# tracker.net
KiCad netlist of a schematic drawn in EAGLE
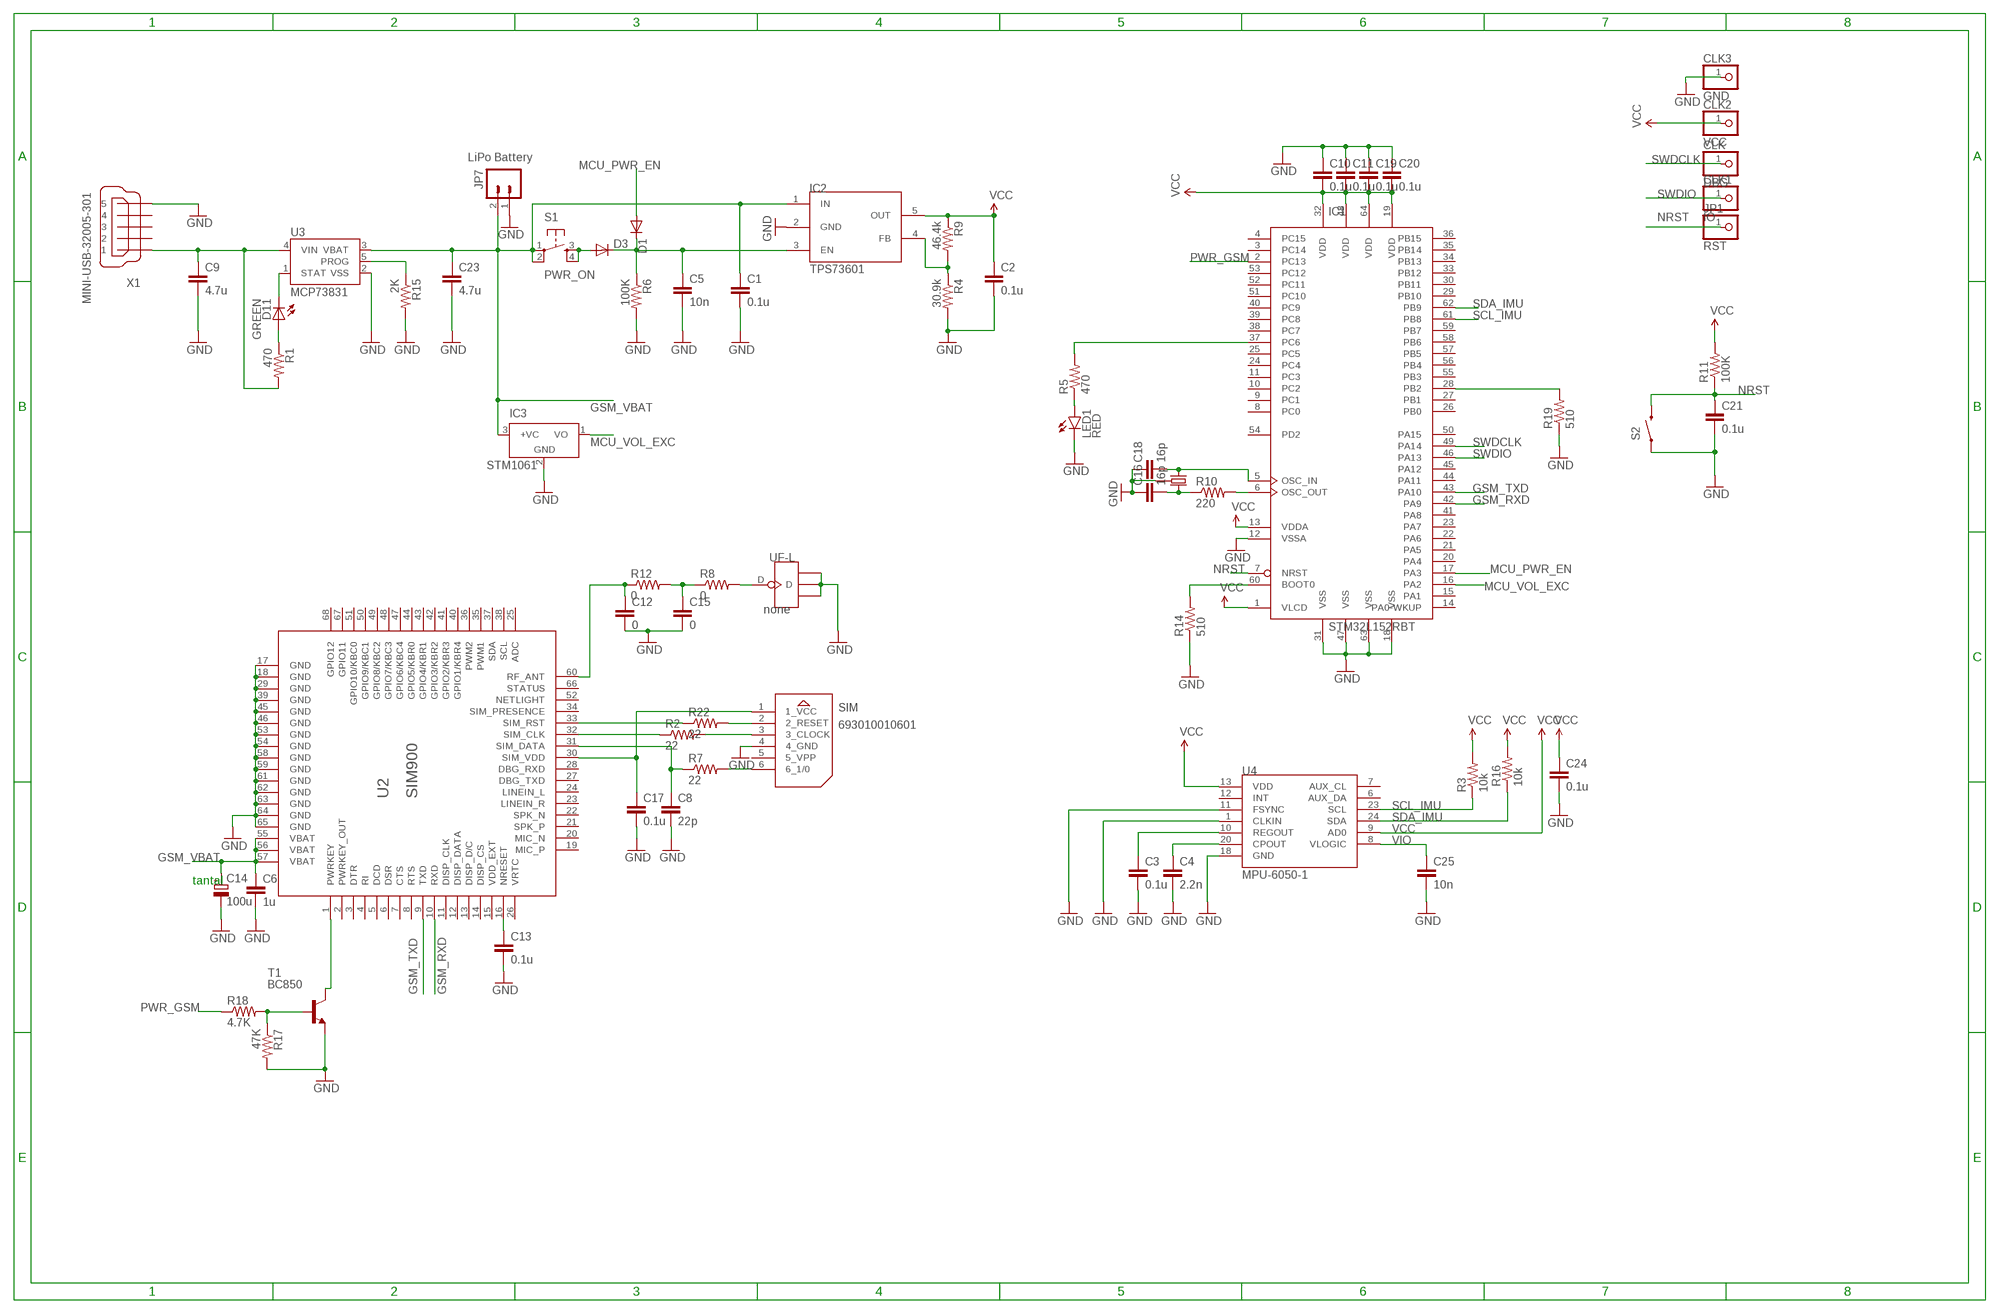
[diagram p0: schematic, sheet 1]

(export (version "E")
  (design (tool "Eeschema 10.0.6"))
  (components
    (comp (ref "C1")
      (value "0.1u")
      (footprint "eagle-import:0805")
      (libsource (lib "eagle-import") (part "CAP0805"))
    )
    (comp (ref "C2")
      (value "0.1u")
      (footprint "eagle-import:0805")
      (libsource (lib "eagle-import") (part "CAP0805"))
    )
    (comp (ref "C3")
      (value "0.1u")
      (footprint "eagle-import:0805")
      (libsource (lib "eagle-import") (part "CAP0805"))
    )
    (comp (ref "C4")
      (value "2.2n")
      (footprint "eagle-import:0805")
      (libsource (lib "eagle-import") (part "CAP0805"))
    )
    (comp (ref "C5")
      (value "10n")
      (footprint "eagle-import:0805")
      (libsource (lib "eagle-import") (part "CAP0805"))
    )
    (comp (ref "C6")
      (value "1u")
      (footprint "eagle-import:0805")
      (libsource (lib "eagle-import") (part "CAP0805"))
    )
    (comp (ref "C8")
      (value "22p")
      (footprint "eagle-import:0805")
      (libsource (lib "eagle-import") (part "CAP0805"))
    )
    (comp (ref "C9")
      (value "4.7u")
      (footprint "eagle-import:0805")
      (libsource (lib "eagle-import") (part "CAP0805"))
    )
    (comp (ref "C10")
      (value "0.1u")
      (footprint "eagle-import:0805")
      (libsource (lib "eagle-import") (part "CAP0805"))
    )
    (comp (ref "C11")
      (value "0.1u")
      (footprint "eagle-import:0805")
      (libsource (lib "eagle-import") (part "CAP0805"))
    )
    (comp (ref "C12")
      (value "0")
      (footprint "eagle-import:0805")
      (libsource (lib "eagle-import") (part "CAP0805"))
    )
    (comp (ref "C13")
      (value "0.1u")
      (footprint "eagle-import:0805")
      (libsource (lib "eagle-import") (part "CAP0805"))
    )
    (comp (ref "C14")
      (value "100u")
      (footprint "eagle-import:C_6032-28R")
      (libsource (lib "eagle-import") (part "CPOL-EUC/6032-28R"))
    )
    (comp (ref "C15")
      (value "0")
      (footprint "eagle-import:0805")
      (libsource (lib "eagle-import") (part "CAP0805"))
    )
    (comp (ref "C16")
      (value "16p")
      (footprint "eagle-import:0603-CAP")
      (libsource (lib "eagle-import") (part "CAP0603-CAP"))
    )
    (comp (ref "C17")
      (value "0.1u")
      (footprint "eagle-import:0805")
      (libsource (lib "eagle-import") (part "CAP0805"))
    )
    (comp (ref "C18")
      (value "16p")
      (footprint "eagle-import:0603-CAP")
      (libsource (lib "eagle-import") (part "CAP0603-CAP"))
    )
    (comp (ref "C19")
      (value "0.1u")
      (footprint "eagle-import:0805")
      (libsource (lib "eagle-import") (part "CAP0805"))
    )
    (comp (ref "C20")
      (value "0.1u")
      (footprint "eagle-import:0805")
      (libsource (lib "eagle-import") (part "CAP0805"))
    )
    (comp (ref "C21")
      (value "0.1u")
      (footprint "eagle-import:0805")
      (libsource (lib "eagle-import") (part "CAP0805"))
    )
    (comp (ref "C23")
      (value "4.7u")
      (footprint "eagle-import:0805")
      (libsource (lib "eagle-import") (part "CAP0805"))
    )
    (comp (ref "C24")
      (value "0.1u")
      (footprint "eagle-import:0805")
      (libsource (lib "eagle-import") (part "CAP0805"))
    )
    (comp (ref "C25")
      (value "10n")
      (footprint "eagle-import:0805")
      (libsource (lib "eagle-import") (part "CAP0805"))
    )
    (comp (ref "CLK")
      (value "DBG")
      (footprint "eagle-import:1X01")
      (libsource (lib "eagle-import") (part "PINHD-1X1"))
    )
    (comp (ref "CLK1")
      (value "IO")
      (footprint "eagle-import:1X01")
      (libsource (lib "eagle-import") (part "PINHD-1X1"))
    )
    (comp (ref "CLK2")
      (value "VCC")
      (footprint "eagle-import:1X01")
      (libsource (lib "eagle-import") (part "PINHD-1X1"))
    )
    (comp (ref "CLK3")
      (value "GND")
      (footprint "eagle-import:1X01")
      (libsource (lib "eagle-import") (part "PINHD-1X1"))
    )
    (comp (ref "D1")
      (value "MBR0520LT")
      (footprint "eagle-import:SOD123")
      (libsource (lib "eagle-import") (part "MBR0520LT"))
    )
    (comp (ref "D3")
      (value "MBR0520LT")
      (footprint "eagle-import:SOD123")
      (libsource (lib "eagle-import") (part "MBR0520LT"))
    )
    (comp (ref "D11")
      (value "GREEN")
      (footprint "eagle-import:LED-0603")
      (libsource (lib "eagle-import") (part "LED0603"))
    )
    (comp (ref "IC1")
      (value "STM32L152RBT")
      (footprint "eagle-import:LQFP64")
      (libsource (lib "eagle-import") (part "STM32L152RTB"))
    )
    (comp (ref "IC2")
      (value "TPS73601")
      (footprint "eagle-import:SOT23")
      (libsource (lib "eagle-import") (part "TPS73601"))
    )
    (comp (ref "IC3")
      (value "LM50")
      (footprint "eagle-import:SOT23")
      (libsource (lib "eagle-import") (part "LM50"))
    )
    (comp (ref "JP1")
      (value "RST")
      (footprint "eagle-import:1X01")
      (libsource (lib "eagle-import") (part "PINHD-1X1"))
    )
    (comp (ref "JP7")
      (value "LiPo Battery")
      (footprint "eagle-import:JST-2-SMD")
      (libsource (lib "eagle-import") (part "M02-JST-2MM-SMT"))
    )
    (comp (ref "LED1")
      (value "RED")
      (footprint "eagle-import:LED-0603")
      (libsource (lib "eagle-import") (part "LED-RED0603"))
    )
    (comp (ref "R1")
      (value "470")
      (footprint "eagle-import:0805")
      (libsource (lib "eagle-import") (part "RESISTOR0805-RES"))
    )
    (comp (ref "R2")
      (value "22")
      (footprint "eagle-import:0805")
      (libsource (lib "eagle-import") (part "RESISTOR0805-RES"))
    )
    (comp (ref "R3")
      (value "10k")
      (footprint "eagle-import:0805")
      (libsource (lib "eagle-import") (part "RESISTOR0805-RES"))
    )
    (comp (ref "R4")
      (value "30.9k")
      (footprint "eagle-import:0805")
      (libsource (lib "eagle-import") (part "RESISTOR0805-RES"))
    )
    (comp (ref "R5")
      (value "470")
      (footprint "eagle-import:0805")
      (libsource (lib "eagle-import") (part "RESISTOR0805-RES"))
    )
    (comp (ref "R6")
      (value "100K")
      (footprint "eagle-import:0805")
      (libsource (lib "eagle-import") (part "RESISTOR0805-RES"))
    )
    (comp (ref "R7")
      (value "22")
      (footprint "eagle-import:0805")
      (libsource (lib "eagle-import") (part "RESISTOR0805-RES"))
    )
    (comp (ref "R8")
      (value "0")
      (footprint "eagle-import:0805")
      (libsource (lib "eagle-import") (part "RESISTOR0805-RES"))
    )
    (comp (ref "R9")
      (value "46.4k")
      (footprint "eagle-import:0805")
      (libsource (lib "eagle-import") (part "RESISTOR0805-RES"))
    )
    (comp (ref "R10")
      (value "220")
      (footprint "eagle-import:0805")
      (libsource (lib "eagle-import") (part "RESISTOR0805-RES"))
    )
    (comp (ref "R11")
      (value "100K")
      (footprint "eagle-import:0805")
      (libsource (lib "eagle-import") (part "RESISTOR0805-RES"))
    )
    (comp (ref "R12")
      (value "0")
      (footprint "eagle-import:0805")
      (libsource (lib "eagle-import") (part "RESISTOR0805-RES"))
    )
    (comp (ref "R14")
      (value "510")
      (footprint "eagle-import:0805")
      (libsource (lib "eagle-import") (part "RESISTOR0805-RES"))
    )
    (comp (ref "R15")
      (value "2K")
      (footprint "eagle-import:0805")
      (libsource (lib "eagle-import") (part "RESISTOR0805-RES"))
    )
    (comp (ref "R16")
      (value "10k")
      (footprint "eagle-import:0805")
      (libsource (lib "eagle-import") (part "RESISTOR0805-RES"))
    )
    (comp (ref "R17")
      (value "47K")
      (footprint "eagle-import:0805")
      (libsource (lib "eagle-import") (part "RESISTOR0805-RES"))
    )
    (comp (ref "R18")
      (value "4.7K")
      (footprint "eagle-import:0805")
      (libsource (lib "eagle-import") (part "RESISTOR0805-RES"))
    )
    (comp (ref "R19")
      (value "510")
      (footprint "eagle-import:0805")
      (libsource (lib "eagle-import") (part "RESISTOR0805-RES"))
    )
    (comp (ref "R22")
      (value "22")
      (footprint "eagle-import:0805")
      (libsource (lib "eagle-import") (part "RESISTOR0805-RES"))
    )
    (comp (ref "S1")
      (value "PWR_ON")
      (footprint "eagle-import:TACTILE-PTH")
      (libsource (lib "eagle-import") (part "TAC_SWITCHPTH"))
    )
    (comp (ref "S2")
      (value "SWITCH-MOMENTARY-2SMD-REDUNDANT")
      (footprint "eagle-import:TACTILE-SWITCH-SMD")
      (libsource (lib "eagle-import") (part "SWITCH-MOMENTARY-2SMD-REDUNDANT"))
    )
    (comp (ref "SIM")
      (value "693010010601")
      (footprint "eagle-import:693010010601")
      (libsource (lib "eagle-import") (part "693010010601"))
    )
    (comp (ref "T1")
      (value "BC850")
      (footprint "eagle-import:SOT23")
      (libsource (lib "eagle-import") (part "BC850"))
    )
    (comp (ref "U$1")
      (value "CRYSTAL-GROUNDED")
      (footprint "eagle-import:CRYSTAL-SMD-5X3")
      (libsource (lib "eagle-import") (part "CRYSTAL-GROUNDED"))
    )
    (comp (ref "U2")
      (value "SIM900")
      (footprint "eagle-import:SIM900")
      (libsource (lib "eagle-import") (part "SIM900"))
    )
    (comp (ref "U3")
      (value "MCP73831")
      (footprint "eagle-import:SOT23-5")
      (libsource (lib "eagle-import") (part "MCP73831"))
    )
    (comp (ref "U4")
      (value "MPU-6050-1")
      (footprint "eagle-import:QFN-24-4MM2")
      (libsource (lib "eagle-import") (part "MPU-6050-1"))
    )
    (comp (ref "UF-L")
      (value "none")
      (footprint "eagle-import:4P-U-FL")
      (libsource (lib "eagle-import") (part "ANTENNA-U-FL"))
    )
    (comp (ref "X1")
      (value "MINI-USB-32005-301")
      (footprint "eagle-import:32005-301")
      (libsource (lib "eagle-import") (part "MINI-USB-32005-301"))
    )
  )
  (nets
    (net (code "1") (name "/GSM_RXD") (class "Default")
      (node (ref "IC1") (pin "42") (pinfunction "PA9_42") (pintype "bidirectional"))
      (node (ref "U2") (pin "10") (pinfunction "RXD_10") (pintype "input"))
    )
    (net (code "2") (name "/GSM_TXD") (class "Default")
      (node (ref "IC1") (pin "43") (pinfunction "PA10_43") (pintype "bidirectional"))
      (node (ref "U2") (pin "9") (pinfunction "TXD_9") (pintype "output"))
    )
    (net (code "3") (name "/GSM_VBAT") (class "Default")
      (node (ref "C1") (pin "1") (pinfunction "1_1") (pintype "passive"))
      (node (ref "C14") (pin "+") (pinfunction "+_+") (pintype "passive"))
      (node (ref "C23") (pin "1") (pinfunction "1_1") (pintype "passive"))
      (node (ref "C6") (pin "1") (pinfunction "1_1") (pintype "passive"))
      (node (ref "IC2") (pin "1") (pinfunction "IN_1") (pintype "power_in"))
      (node (ref "IC3") (pin "3") (pinfunction "+VC_3") (pintype "input"))
      (node (ref "JP7") (pin "2") (pinfunction "2_2") (pintype "passive"))
      (node (ref "S1") (pin "1") (pinfunction "1_1") (pintype "passive"))
      (node (ref "S1") (pin "2") (pinfunction "2_2") (pintype "passive"))
      (node (ref "U2") (pin "55") (pinfunction "VBAT_55") (pintype "power_in"))
      (node (ref "U2") (pin "56") (pinfunction "VBAT_56") (pintype "power_in"))
      (node (ref "U2") (pin "57") (pinfunction "VBAT_57") (pintype "power_in"))
      (node (ref "U3") (pin "3") (pinfunction "VBAT_3") (pintype "power_in"))
    )
    (net (code "4") (name "/MCU_PWR_EN") (class "Default")
      (node (ref "D1") (pin "A") (pinfunction "A_A") (pintype "passive"))
      (node (ref "IC1") (pin "17") (pinfunction "PA3_17") (pintype "bidirectional"))
    )
    (net (code "5") (name "/MCU_VOL_EXC") (class "Default")
      (node (ref "IC1") (pin "16") (pinfunction "PA2_16") (pintype "bidirectional"))
      (node (ref "IC3") (pin "1") (pinfunction "VO_1") (pintype "input"))
    )
    (net (code "6") (name "/NRST") (class "Default")
      (node (ref "C21") (pin "1") (pinfunction "1_1") (pintype "passive"))
      (node (ref "IC1") (pin "7") (pinfunction "NRST_7") (pintype "bidirectional"))
      (node (ref "JP1") (pin "1") (pinfunction "1_1") (pintype "passive"))
      (node (ref "R11") (pin "1") (pinfunction "1_1") (pintype "passive"))
      (node (ref "S2") (pin "3") (pinfunction "2_3") (pintype "passive"))
      (node (ref "S2") (pin "4") (pinfunction "2_4") (pintype "passive"))
    )
    (net (code "7") (name "/PWR_GSM") (class "Default")
      (node (ref "IC1") (pin "2") (pinfunction "PC13_2") (pintype "bidirectional"))
      (node (ref "R18") (pin "1") (pinfunction "1_1") (pintype "passive"))
    )
    (net (code "8") (name "/SCL_IMU") (class "Default")
      (node (ref "IC1") (pin "61") (pinfunction "PB8_61") (pintype "bidirectional"))
      (node (ref "R3") (pin "1") (pinfunction "1_1") (pintype "passive"))
      (node (ref "U4") (pin "23") (pinfunction "SCL_23") (pintype "bidirectional"))
    )
    (net (code "9") (name "/SDA_IMU") (class "Default")
      (node (ref "IC1") (pin "62") (pinfunction "PB9_62") (pintype "bidirectional"))
      (node (ref "R16") (pin "1") (pinfunction "1_1") (pintype "passive"))
      (node (ref "U4") (pin "24") (pinfunction "SDA_24") (pintype "bidirectional"))
    )
    (net (code "10") (name "/SWDCLK") (class "Default")
      (node (ref "CLK") (pin "1") (pinfunction "1_1") (pintype "passive"))
      (node (ref "IC1") (pin "49") (pinfunction "PA14_49") (pintype "bidirectional"))
    )
    (net (code "11") (name "/SWDIO") (class "Default")
      (node (ref "CLK1") (pin "1") (pinfunction "1_1") (pintype "passive"))
      (node (ref "IC1") (pin "46") (pinfunction "PA13_46") (pintype "bidirectional"))
    )
    (net (code "12") (name "/VIO") (class "Default")
      (node (ref "C25") (pin "1") (pinfunction "1_1") (pintype "passive"))
      (node (ref "U4") (pin "8") (pinfunction "VLOGIC_8") (pintype "bidirectional"))
    )
    (net (code "13") (name "GND") (class "Default")
      (node (ref "C1") (pin "2") (pinfunction "2_2") (pintype "passive"))
      (node (ref "C10") (pin "1") (pinfunction "1_1") (pintype "passive"))
      (node (ref "C11") (pin "1") (pinfunction "1_1") (pintype "passive"))
      (node (ref "C12") (pin "2") (pinfunction "2_2") (pintype "passive"))
      (node (ref "C13") (pin "2") (pinfunction "2_2") (pintype "passive"))
      (node (ref "C14") (pin "-") (pinfunction "-_-") (pintype "passive"))
      (node (ref "C15") (pin "2") (pinfunction "2_2") (pintype "passive"))
      (node (ref "C16") (pin "1") (pinfunction "1_1") (pintype "passive"))
      (node (ref "C17") (pin "2") (pinfunction "2_2") (pintype "passive"))
      (node (ref "C18") (pin "1") (pinfunction "1_1") (pintype "passive"))
      (node (ref "C19") (pin "1") (pinfunction "1_1") (pintype "passive"))
      (node (ref "C2") (pin "2") (pinfunction "2_2") (pintype "passive"))
      (node (ref "C20") (pin "1") (pinfunction "1_1") (pintype "passive"))
      (node (ref "C21") (pin "2") (pinfunction "2_2") (pintype "passive"))
      (node (ref "C23") (pin "2") (pinfunction "2_2") (pintype "passive"))
      (node (ref "C24") (pin "2") (pinfunction "2_2") (pintype "passive"))
      (node (ref "C25") (pin "2") (pinfunction "2_2") (pintype "passive"))
      (node (ref "C3") (pin "2") (pinfunction "2_2") (pintype "passive"))
      (node (ref "C4") (pin "2") (pinfunction "2_2") (pintype "passive"))
      (node (ref "C5") (pin "2") (pinfunction "2_2") (pintype "passive"))
      (node (ref "C6") (pin "2") (pinfunction "2_2") (pintype "passive"))
      (node (ref "C8") (pin "2") (pinfunction "2_2") (pintype "passive"))
      (node (ref "C9") (pin "2") (pinfunction "2_2") (pintype "passive"))
      (node (ref "CLK3") (pin "1") (pinfunction "1_1") (pintype "passive"))
      (node (ref "IC1") (pin "12") (pinfunction "VSSA_12") (pintype "power_in"))
      (node (ref "IC1") (pin "18") (pinfunction "VSS_18") (pintype "power_in"))
      (node (ref "IC1") (pin "31") (pinfunction "VSS_31") (pintype "power_in"))
      (node (ref "IC1") (pin "47") (pinfunction "VSS_47") (pintype "power_in"))
      (node (ref "IC1") (pin "63") (pinfunction "VSS_63") (pintype "power_in"))
      (node (ref "IC2") (pin "2") (pinfunction "GND_2") (pintype "power_in"))
      (node (ref "IC3") (pin "2") (pinfunction "GND_2") (pintype "power_in"))
      (node (ref "JP7") (pin "1") (pinfunction "1_1") (pintype "passive"))
      (node (ref "LED1") (pin "C") (pinfunction "C_C") (pintype "passive"))
      (node (ref "R14") (pin "1") (pinfunction "1_1") (pintype "passive"))
      (node (ref "R15") (pin "2") (pinfunction "2_2") (pintype "passive"))
      (node (ref "R17") (pin "2") (pinfunction "2_2") (pintype "passive"))
      (node (ref "R19") (pin "1") (pinfunction "1_1") (pintype "passive"))
      (node (ref "R4") (pin "2") (pinfunction "2_2") (pintype "passive"))
      (node (ref "R6") (pin "2") (pinfunction "2_2") (pintype "passive"))
      (node (ref "S2") (pin "1") (pinfunction "1_1") (pintype "passive"))
      (node (ref "S2") (pin "2") (pinfunction "1_2") (pintype "passive"))
      (node (ref "SIM") (pin "4") (pinfunction "4_GND_4") (pintype "bidirectional"))
      (node (ref "T1") (pin "2") (pinfunction "E_2") (pintype "passive"))
      (node (ref "U$1") (pin "2") (pinfunction "3_2") (pintype "passive"))
      (node (ref "U$1") (pin "4") (pinfunction "3_4") (pintype "passive"))
      (node (ref "U2") (pin "17") (pinfunction "GND_17") (pintype "power_in"))
      (node (ref "U2") (pin "18") (pinfunction "GND_18") (pintype "power_in"))
      (node (ref "U2") (pin "29") (pinfunction "GND_29") (pintype "power_in"))
      (node (ref "U2") (pin "39") (pinfunction "GND_39") (pintype "power_in"))
      (node (ref "U2") (pin "45") (pinfunction "GND_45") (pintype "power_in"))
      (node (ref "U2") (pin "46") (pinfunction "GND_46") (pintype "power_in"))
      (node (ref "U2") (pin "53") (pinfunction "GND_53") (pintype "power_in"))
      (node (ref "U2") (pin "54") (pinfunction "GND_54") (pintype "power_in"))
      (node (ref "U2") (pin "58") (pinfunction "GND_58") (pintype "power_in"))
      (node (ref "U2") (pin "59") (pinfunction "GND_59") (pintype "power_in"))
      (node (ref "U2") (pin "61") (pinfunction "GND_61") (pintype "power_in"))
      (node (ref "U2") (pin "62") (pinfunction "GND_62") (pintype "power_in"))
      (node (ref "U2") (pin "63") (pinfunction "GND_63") (pintype "power_in"))
      (node (ref "U2") (pin "64") (pinfunction "GND_64") (pintype "power_in"))
      (node (ref "U2") (pin "65") (pinfunction "GND_65") (pintype "power_in"))
      (node (ref "U3") (pin "2") (pinfunction "VSS_2") (pintype "power_in"))
      (node (ref "U4") (pin "1") (pinfunction "CLKIN_1") (pintype "bidirectional"))
      (node (ref "U4") (pin "11") (pinfunction "FSYNC_11") (pintype "bidirectional"))
      (node (ref "U4") (pin "18") (pinfunction "GND_18") (pintype "bidirectional"))
      (node (ref "UF-L") (pin "GND1") (pinfunction "GND1_GND1") (pintype "bidirectional"))
      (node (ref "UF-L") (pin "GND2") (pinfunction "GND2_GND2") (pintype "bidirectional"))
      (node (ref "UF-L") (pin "GND3") (pinfunction "GND3_GND3") (pintype "bidirectional"))
      (node (ref "X1") (pin "5") (pinfunction "5_5") (pintype "passive"))
    )
    (net (code "14") (name "Net-(C15-Pad1)") (class "Default")
      (node (ref "C15") (pin "1") (pinfunction "1_1") (pintype "passive"))
      (node (ref "R12") (pin "2") (pinfunction "2_2") (pintype "passive"))
      (node (ref "R8") (pin "1") (pinfunction "1_1") (pintype "passive"))
    )
    (net (code "15") (name "Net-(D3-PadA)") (class "Default")
      (node (ref "D3") (pin "A") (pinfunction "A_A") (pintype "passive"))
      (node (ref "S1") (pin "3") (pinfunction "3_3") (pintype "passive"))
      (node (ref "S1") (pin "4") (pinfunction "4_4") (pintype "passive"))
    )
    (net (code "16") (name "Net-(D11-PadA)") (class "Default")
      (node (ref "D11") (pin "A") (pinfunction "A_A") (pintype "passive"))
      (node (ref "R1") (pin "1") (pinfunction "1_1") (pintype "passive"))
    )
    (net (code "17") (name "Net-(IC1A-BOOT0)") (class "Default")
      (node (ref "IC1") (pin "60") (pinfunction "BOOT0_60") (pintype "input"))
      (node (ref "R14") (pin "2") (pinfunction "2_2") (pintype "passive"))
    )
    (net (code "18") (name "Net-(IC1A-OSC_IN)") (class "Default")
      (node (ref "C18") (pin "2") (pinfunction "2_2") (pintype "passive"))
      (node (ref "IC1") (pin "5") (pinfunction "OSC_IN_5") (pintype "bidirectional"))
      (node (ref "U$1") (pin "3") (pinfunction "1_3") (pintype "passive"))
    )
    (net (code "19") (name "Net-(IC1A-OSC_OUT)") (class "Default")
      (node (ref "IC1") (pin "6") (pinfunction "OSC_OUT_6") (pintype "bidirectional"))
      (node (ref "R10") (pin "2") (pinfunction "2_2") (pintype "passive"))
    )
    (net (code "20") (name "Net-(IC1A-PB2)") (class "Default")
      (node (ref "IC1") (pin "28") (pinfunction "PB2_28") (pintype "bidirectional"))
      (node (ref "R19") (pin "2") (pinfunction "2_2") (pintype "passive"))
    )
    (net (code "21") (name "Net-(IC1A-PC6)") (class "Default")
      (node (ref "IC1") (pin "37") (pinfunction "PC6_37") (pintype "bidirectional"))
      (node (ref "R5") (pin "2") (pinfunction "2_2") (pintype "passive"))
    )
    (net (code "22") (name "Net-(IC2-EN)") (class "Default")
      (node (ref "C5") (pin "1") (pinfunction "1_1") (pintype "passive"))
      (node (ref "D1") (pin "C") (pinfunction "C_C") (pintype "passive"))
      (node (ref "D3") (pin "C") (pinfunction "C_C") (pintype "passive"))
      (node (ref "IC2") (pin "3") (pinfunction "EN_3") (pintype "passive"))
      (node (ref "R6") (pin "1") (pinfunction "1_1") (pintype "passive"))
    )
    (net (code "23") (name "Net-(IC2-FB)") (class "Default")
      (node (ref "IC2") (pin "4") (pinfunction "FB_4") (pintype "power_in"))
      (node (ref "R4") (pin "1") (pinfunction "1_1") (pintype "passive"))
      (node (ref "R9") (pin "2") (pinfunction "2_2") (pintype "passive"))
    )
    (net (code "24") (name "Net-(LED1-PadA)") (class "Default")
      (node (ref "LED1") (pin "A") (pinfunction "A_A") (pintype "passive"))
      (node (ref "R5") (pin "1") (pinfunction "1_1") (pintype "passive"))
    )
    (net (code "25") (name "Net-(R8-Pad2)") (class "Default")
      (node (ref "R8") (pin "2") (pinfunction "2_2") (pintype "passive"))
      (node (ref "UF-L") (pin "D") (pinfunction "D_D") (pintype "bidirectional"))
    )
    (net (code "26") (name "Net-(SIM-1_VCC)") (class "Default")
      (node (ref "C17") (pin "1") (pinfunction "1_1") (pintype "passive"))
      (node (ref "SIM") (pin "1") (pinfunction "1_VCC_1") (pintype "bidirectional"))
      (node (ref "U2") (pin "30") (pinfunction "SIM_VDD_30") (pintype "output"))
    )
    (net (code "27") (name "Net-(SIM-2_RESET)") (class "Default")
      (node (ref "R22") (pin "2") (pinfunction "2_2") (pintype "passive"))
      (node (ref "SIM") (pin "2") (pinfunction "2_RESET_2") (pintype "bidirectional"))
    )
    (net (code "28") (name "Net-(SIM-3_CLOCK)") (class "Default")
      (node (ref "R2") (pin "2") (pinfunction "2_2") (pintype "passive"))
      (node (ref "SIM") (pin "3") (pinfunction "3_CLOCK_3") (pintype "bidirectional"))
    )
    (net (code "29") (name "Net-(SIM-6_1{slash}0)") (class "Default")
      (node (ref "R7") (pin "2") (pinfunction "2_2") (pintype "passive"))
      (node (ref "SIM") (pin "6") (pinfunction "6_1/0_6") (pintype "bidirectional"))
    )
    (net (code "30") (name "Net-(T1-B)") (class "Default")
      (node (ref "R17") (pin "1") (pinfunction "1_1") (pintype "passive"))
      (node (ref "R18") (pin "2") (pinfunction "2_2") (pintype "passive"))
      (node (ref "T1") (pin "1") (pinfunction "B_1") (pintype "passive"))
    )
    (net (code "31") (name "Net-(T1-C)") (class "Default")
      (node (ref "T1") (pin "3") (pinfunction "C_3") (pintype "passive"))
      (node (ref "U2") (pin "1") (pinfunction "PWRKEY_1") (pintype "input"))
    )
    (net (code "32") (name "Net-(U$1-2)") (class "Default")
      (node (ref "C16") (pin "2") (pinfunction "2_2") (pintype "passive"))
      (node (ref "R10") (pin "1") (pinfunction "1_1") (pintype "passive"))
      (node (ref "U$1") (pin "1") (pinfunction "2_1") (pintype "passive"))
    )
    (net (code "33") (name "Net-(U2-NRESET)") (class "Default")
      (node (ref "C13") (pin "1") (pinfunction "1_1") (pintype "passive"))
      (node (ref "U2") (pin "16") (pinfunction "NRESET_16") (pintype "input"))
    )
    (net (code "34") (name "Net-(U2-RF_ANT)") (class "Default")
      (node (ref "C12") (pin "1") (pinfunction "1_1") (pintype "passive"))
      (node (ref "R12") (pin "1") (pinfunction "1_1") (pintype "passive"))
      (node (ref "U2") (pin "60") (pinfunction "RF_ANT_60") (pintype "bidirectional"))
    )
    (net (code "35") (name "Net-(U2-SIM_CLK)") (class "Default")
      (node (ref "R2") (pin "1") (pinfunction "1_1") (pintype "passive"))
      (node (ref "U2") (pin "32") (pinfunction "SIM_CLK_32") (pintype "output"))
    )
    (net (code "36") (name "Net-(U2-SIM_DATA)") (class "Default")
      (node (ref "C8") (pin "1") (pinfunction "1_1") (pintype "passive"))
      (node (ref "R7") (pin "1") (pinfunction "1_1") (pintype "passive"))
      (node (ref "U2") (pin "31") (pinfunction "SIM_DATA_31") (pintype "bidirectional"))
    )
    (net (code "37") (name "Net-(U2-SIM_RST)") (class "Default")
      (node (ref "R22") (pin "1") (pinfunction "1_1") (pintype "passive"))
      (node (ref "U2") (pin "33") (pinfunction "SIM_RST_33") (pintype "output"))
    )
    (net (code "38") (name "Net-(U3-PROG)") (class "Default")
      (node (ref "R15") (pin "1") (pinfunction "1_1") (pintype "passive"))
      (node (ref "U3") (pin "5") (pinfunction "PROG_5") (pintype "input"))
    )
    (net (code "39") (name "Net-(U3-STAT)") (class "Default")
      (node (ref "D11") (pin "C") (pinfunction "C_C") (pintype "passive"))
      (node (ref "U3") (pin "1") (pinfunction "STAT_1") (pintype "output"))
    )
    (net (code "40") (name "Net-(U3-VIN)") (class "Default")
      (node (ref "C9") (pin "1") (pinfunction "1_1") (pintype "passive"))
      (node (ref "R1") (pin "2") (pinfunction "2_2") (pintype "passive"))
      (node (ref "U3") (pin "4") (pinfunction "VIN_4") (pintype "power_in"))
      (node (ref "X1") (pin "1") (pinfunction "1_1") (pintype "passive"))
    )
    (net (code "41") (name "Net-(U4-CPOUT)") (class "Default")
      (node (ref "C4") (pin "1") (pinfunction "1_1") (pintype "passive"))
      (node (ref "U4") (pin "20") (pinfunction "CPOUT_20") (pintype "bidirectional"))
    )
    (net (code "42") (name "Net-(U4-REGOUT)") (class "Default")
      (node (ref "C3") (pin "1") (pinfunction "1_1") (pintype "passive"))
      (node (ref "U4") (pin "10") (pinfunction "REGOUT_10") (pintype "bidirectional"))
    )
    (net (code "43") (name "VCC") (class "Default")
      (node (ref "C10") (pin "2") (pinfunction "2_2") (pintype "passive"))
      (node (ref "C11") (pin "2") (pinfunction "2_2") (pintype "passive"))
      (node (ref "C19") (pin "2") (pinfunction "2_2") (pintype "passive"))
      (node (ref "C2") (pin "1") (pinfunction "1_1") (pintype "passive"))
      (node (ref "C20") (pin "2") (pinfunction "2_2") (pintype "passive"))
      (node (ref "C24") (pin "1") (pinfunction "1_1") (pintype "passive"))
      (node (ref "CLK2") (pin "1") (pinfunction "1_1") (pintype "passive"))
      (node (ref "IC1") (pin "1") (pinfunction "VLCD_1") (pintype "power_in"))
      (node (ref "IC1") (pin "13") (pinfunction "VDDA_13") (pintype "power_in"))
      (node (ref "IC1") (pin "19") (pinfunction "VDD_19") (pintype "power_in"))
      (node (ref "IC1") (pin "32") (pinfunction "VDD_32") (pintype "power_in"))
      (node (ref "IC1") (pin "48") (pinfunction "VDD_48") (pintype "power_in"))
      (node (ref "IC1") (pin "64") (pinfunction "VDD_64") (pintype "power_in"))
      (node (ref "IC2") (pin "5") (pinfunction "OUT_5") (pintype "power_in"))
      (node (ref "R11") (pin "2") (pinfunction "2_2") (pintype "passive"))
      (node (ref "R16") (pin "2") (pinfunction "2_2") (pintype "passive"))
      (node (ref "R3") (pin "2") (pinfunction "2_2") (pintype "passive"))
      (node (ref "R9") (pin "1") (pinfunction "1_1") (pintype "passive"))
      (node (ref "U4") (pin "13") (pinfunction "VDD_13") (pintype "bidirectional"))
      (node (ref "U4") (pin "9") (pinfunction "AD0_9") (pintype "bidirectional"))
    )
    (net (code "44") (name "unconnected-(IC1A-PA0-WKUP-Pad14)") (class "Default")
      (node (ref "IC1") (pin "14") (pinfunction "PA0-WKUP_14") (pintype "bidirectional"))
    )
    (net (code "45") (name "unconnected-(IC1A-PA1-Pad15)") (class "Default")
      (node (ref "IC1") (pin "15") (pinfunction "PA1_15") (pintype "bidirectional"))
    )
    (net (code "46") (name "unconnected-(IC1A-PA4-Pad20)") (class "Default")
      (node (ref "IC1") (pin "20") (pinfunction "PA4_20") (pintype "bidirectional"))
    )
    (net (code "47") (name "unconnected-(IC1A-PA5-Pad21)") (class "Default")
      (node (ref "IC1") (pin "21") (pinfunction "PA5_21") (pintype "bidirectional"))
    )
    (net (code "48") (name "unconnected-(IC1A-PA6-Pad22)") (class "Default")
      (node (ref "IC1") (pin "22") (pinfunction "PA6_22") (pintype "bidirectional"))
    )
    (net (code "49") (name "unconnected-(IC1A-PA7-Pad23)") (class "Default")
      (node (ref "IC1") (pin "23") (pinfunction "PA7_23") (pintype "bidirectional"))
    )
    (net (code "50") (name "unconnected-(IC1A-PA8-Pad41)") (class "Default")
      (node (ref "IC1") (pin "41") (pinfunction "PA8_41") (pintype "bidirectional"))
    )
    (net (code "51") (name "unconnected-(IC1A-PA11-Pad44)") (class "Default")
      (node (ref "IC1") (pin "44") (pinfunction "PA11_44") (pintype "bidirectional"))
    )
    (net (code "52") (name "unconnected-(IC1A-PA12-Pad45)") (class "Default")
      (node (ref "IC1") (pin "45") (pinfunction "PA12_45") (pintype "bidirectional"))
    )
    (net (code "53") (name "unconnected-(IC1A-PA15-Pad50)") (class "Default")
      (node (ref "IC1") (pin "50") (pinfunction "PA15_50") (pintype "bidirectional"))
    )
    (net (code "54") (name "unconnected-(IC1A-PB0-Pad26)") (class "Default")
      (node (ref "IC1") (pin "26") (pinfunction "PB0_26") (pintype "bidirectional"))
    )
    (net (code "55") (name "unconnected-(IC1A-PB1-Pad27)") (class "Default")
      (node (ref "IC1") (pin "27") (pinfunction "PB1_27") (pintype "bidirectional"))
    )
    (net (code "56") (name "unconnected-(IC1A-PB3-Pad55)") (class "Default")
      (node (ref "IC1") (pin "55") (pinfunction "PB3_55") (pintype "bidirectional"))
    )
    (net (code "57") (name "unconnected-(IC1A-PB4-Pad56)") (class "Default")
      (node (ref "IC1") (pin "56") (pinfunction "PB4_56") (pintype "bidirectional"))
    )
    (net (code "58") (name "unconnected-(IC1A-PB5-Pad57)") (class "Default")
      (node (ref "IC1") (pin "57") (pinfunction "PB5_57") (pintype "bidirectional"))
    )
    (net (code "59") (name "unconnected-(IC1A-PB6-Pad58)") (class "Default")
      (node (ref "IC1") (pin "58") (pinfunction "PB6_58") (pintype "bidirectional"))
    )
    (net (code "60") (name "unconnected-(IC1A-PB7-Pad59)") (class "Default")
      (node (ref "IC1") (pin "59") (pinfunction "PB7_59") (pintype "bidirectional"))
    )
    (net (code "61") (name "unconnected-(IC1A-PB10-Pad29)") (class "Default")
      (node (ref "IC1") (pin "29") (pinfunction "PB10_29") (pintype "bidirectional"))
    )
    (net (code "62") (name "unconnected-(IC1A-PB11-Pad30)") (class "Default")
      (node (ref "IC1") (pin "30") (pinfunction "PB11_30") (pintype "bidirectional"))
    )
    (net (code "63") (name "unconnected-(IC1A-PB12-Pad33)") (class "Default")
      (node (ref "IC1") (pin "33") (pinfunction "PB12_33") (pintype "bidirectional"))
    )
    (net (code "64") (name "unconnected-(IC1A-PB13-Pad34)") (class "Default")
      (node (ref "IC1") (pin "34") (pinfunction "PB13_34") (pintype "bidirectional"))
    )
    (net (code "65") (name "unconnected-(IC1A-PB14-Pad35)") (class "Default")
      (node (ref "IC1") (pin "35") (pinfunction "PB14_35") (pintype "bidirectional"))
    )
    (net (code "66") (name "unconnected-(IC1A-PB15-Pad36)") (class "Default")
      (node (ref "IC1") (pin "36") (pinfunction "PB15_36") (pintype "bidirectional"))
    )
    (net (code "67") (name "unconnected-(IC1A-PC0-Pad8)") (class "Default")
      (node (ref "IC1") (pin "8") (pinfunction "PC0_8") (pintype "bidirectional"))
    )
    (net (code "68") (name "unconnected-(IC1A-PC1-Pad9)") (class "Default")
      (node (ref "IC1") (pin "9") (pinfunction "PC1_9") (pintype "bidirectional"))
    )
    (net (code "69") (name "unconnected-(IC1A-PC2-Pad10)") (class "Default")
      (node (ref "IC1") (pin "10") (pinfunction "PC2_10") (pintype "bidirectional"))
    )
    (net (code "70") (name "unconnected-(IC1A-PC3-Pad11)") (class "Default")
      (node (ref "IC1") (pin "11") (pinfunction "PC3_11") (pintype "bidirectional"))
    )
    (net (code "71") (name "unconnected-(IC1A-PC4-Pad24)") (class "Default")
      (node (ref "IC1") (pin "24") (pinfunction "PC4_24") (pintype "bidirectional"))
    )
    (net (code "72") (name "unconnected-(IC1A-PC5-Pad25)") (class "Default")
      (node (ref "IC1") (pin "25") (pinfunction "PC5_25") (pintype "bidirectional"))
    )
    (net (code "73") (name "unconnected-(IC1A-PC7-Pad38)") (class "Default")
      (node (ref "IC1") (pin "38") (pinfunction "PC7_38") (pintype "bidirectional"))
    )
    (net (code "74") (name "unconnected-(IC1A-PC8-Pad39)") (class "Default")
      (node (ref "IC1") (pin "39") (pinfunction "PC8_39") (pintype "bidirectional"))
    )
    (net (code "75") (name "unconnected-(IC1A-PC9-Pad40)") (class "Default")
      (node (ref "IC1") (pin "40") (pinfunction "PC9_40") (pintype "bidirectional"))
    )
    (net (code "76") (name "unconnected-(IC1A-PC10-Pad51)") (class "Default")
      (node (ref "IC1") (pin "51") (pinfunction "PC10_51") (pintype "bidirectional"))
    )
    (net (code "77") (name "unconnected-(IC1A-PC11-Pad52)") (class "Default")
      (node (ref "IC1") (pin "52") (pinfunction "PC11_52") (pintype "bidirectional"))
    )
    (net (code "78") (name "unconnected-(IC1A-PC12-Pad53)") (class "Default")
      (node (ref "IC1") (pin "53") (pinfunction "PC12_53") (pintype "bidirectional"))
    )
    (net (code "79") (name "unconnected-(IC1A-PC14-Pad3)") (class "Default")
      (node (ref "IC1") (pin "3") (pinfunction "PC14_3") (pintype "bidirectional"))
    )
    (net (code "80") (name "unconnected-(IC1A-PC15-Pad4)") (class "Default")
      (node (ref "IC1") (pin "4") (pinfunction "PC15_4") (pintype "bidirectional"))
    )
    (net (code "81") (name "unconnected-(IC1A-PD2-Pad54)") (class "Default")
      (node (ref "IC1") (pin "54") (pinfunction "PD2_54") (pintype "bidirectional"))
    )
    (net (code "82") (name "unconnected-(SIM-5_VPP-Pad5)") (class "Default")
      (node (ref "SIM") (pin "5") (pinfunction "5_VPP_5") (pintype "bidirectional"))
    )
    (net (code "83") (name "unconnected-(U2-ADC-Pad25)") (class "Default")
      (node (ref "U2") (pin "25") (pinfunction "ADC_25") (pintype "input"))
    )
    (net (code "84") (name "unconnected-(U2-CTS-Pad7)") (class "Default")
      (node (ref "U2") (pin "7") (pinfunction "CTS_7") (pintype "output"))
    )
    (net (code "85") (name "unconnected-(U2-DBG_RXD-Pad28)") (class "Default")
      (node (ref "U2") (pin "28") (pinfunction "DBG_RXD_28") (pintype "input"))
    )
    (net (code "86") (name "unconnected-(U2-DBG_TXD-Pad27)") (class "Default")
      (node (ref "U2") (pin "27") (pinfunction "DBG_TXD_27") (pintype "output"))
    )
    (net (code "87") (name "unconnected-(U2-DCD-Pad5)") (class "Default")
      (node (ref "U2") (pin "5") (pinfunction "DCD_5") (pintype "output"))
    )
    (net (code "88") (name "unconnected-(U2-DISP_CLK-Pad11)") (class "Default")
      (node (ref "U2") (pin "11") (pinfunction "DISP_CLK_11") (pintype "output"))
    )
    (net (code "89") (name "unconnected-(U2-DISP_CS-Pad14)") (class "Default")
      (node (ref "U2") (pin "14") (pinfunction "DISP_CS_14") (pintype "output"))
    )
    (net (code "90") (name "unconnected-(U2-DISP_DATA-Pad12)") (class "Default")
      (node (ref "U2") (pin "12") (pinfunction "DISP_DATA_12") (pintype "bidirectional"))
    )
    (net (code "91") (name "unconnected-(U2-DISP_D{slash}C-Pad13)") (class "Default")
      (node (ref "U2") (pin "13") (pinfunction "DISP_D/C_13") (pintype "output"))
    )
    (net (code "92") (name "unconnected-(U2-DSR-Pad6)") (class "Default")
      (node (ref "U2") (pin "6") (pinfunction "DSR_6") (pintype "output"))
    )
    (net (code "93") (name "unconnected-(U2-DTR-Pad3)") (class "Default")
      (node (ref "U2") (pin "3") (pinfunction "DTR_3") (pintype "input"))
    )
    (net (code "94") (name "unconnected-(U2-GPIO1{slash}KBR4-Pad40)") (class "Default")
      (node (ref "U2") (pin "40") (pinfunction "GPIO1/KBR4_40") (pintype "output"))
    )
    (net (code "95") (name "unconnected-(U2-GPIO2{slash}KBR3-Pad41)") (class "Default")
      (node (ref "U2") (pin "41") (pinfunction "GPIO2/KBR3_41") (pintype "output"))
    )
    (net (code "96") (name "unconnected-(U2-GPIO3{slash}KBR2-Pad42)") (class "Default")
      (node (ref "U2") (pin "42") (pinfunction "GPIO3/KBR2_42") (pintype "output"))
    )
    (net (code "97") (name "unconnected-(U2-GPIO4{slash}KBR1-Pad43)") (class "Default")
      (node (ref "U2") (pin "43") (pinfunction "GPIO4/KBR1_43") (pintype "output"))
    )
    (net (code "98") (name "unconnected-(U2-GPIO5{slash}KBR0-Pad44)") (class "Default")
      (node (ref "U2") (pin "44") (pinfunction "GPIO5/KBR0_44") (pintype "output"))
    )
    (net (code "99") (name "unconnected-(U2-GPIO6{slash}KBC4-Pad47)") (class "Default")
      (node (ref "U2") (pin "47") (pinfunction "GPIO6/KBC4_47") (pintype "input"))
    )
    (net (code "100") (name "unconnected-(U2-GPIO7{slash}KBC3-Pad48)") (class "Default")
      (node (ref "U2") (pin "48") (pinfunction "GPIO7/KBC3_48") (pintype "bidirectional"))
    )
    (net (code "101") (name "unconnected-(U2-GPIO8{slash}KBC2-Pad49)") (class "Default")
      (node (ref "U2") (pin "49") (pinfunction "GPIO8/KBC2_49") (pintype "input"))
    )
    (net (code "102") (name "unconnected-(U2-GPIO9{slash}KBC1-Pad50)") (class "Default")
      (node (ref "U2") (pin "50") (pinfunction "GPIO9/KBC1_50") (pintype "input"))
    )
    (net (code "103") (name "unconnected-(U2-GPIO10{slash}KBC0-Pad51)") (class "Default")
      (node (ref "U2") (pin "51") (pinfunction "GPIO10/KBC0_51") (pintype "bidirectional"))
    )
    (net (code "104") (name "unconnected-(U2-GPIO11-Pad67)") (class "Default")
      (node (ref "U2") (pin "67") (pinfunction "GPIO11_67") (pintype "bidirectional"))
    )
    (net (code "105") (name "unconnected-(U2-GPIO12-Pad68)") (class "Default")
      (node (ref "U2") (pin "68") (pinfunction "GPIO12_68") (pintype "bidirectional"))
    )
    (net (code "106") (name "unconnected-(U2-LINEIN_L-Pad24)") (class "Default")
      (node (ref "U2") (pin "24") (pinfunction "LINEIN_L_24") (pintype "input"))
    )
    (net (code "107") (name "unconnected-(U2-LINEIN_R-Pad23)") (class "Default")
      (node (ref "U2") (pin "23") (pinfunction "LINEIN_R_23") (pintype "input"))
    )
    (net (code "108") (name "unconnected-(U2-MIC_N-Pad20)") (class "Default")
      (node (ref "U2") (pin "20") (pinfunction "MIC_N_20") (pintype "input"))
    )
    (net (code "109") (name "unconnected-(U2-MIC_P-Pad19)") (class "Default")
      (node (ref "U2") (pin "19") (pinfunction "MIC_P_19") (pintype "input"))
    )
    (net (code "110") (name "unconnected-(U2-NETLIGHT-Pad52)") (class "Default")
      (node (ref "U2") (pin "52") (pinfunction "NETLIGHT_52") (pintype "output"))
    )
    (net (code "111") (name "unconnected-(U2-PWM1-Pad35)") (class "Default")
      (node (ref "U2") (pin "35") (pinfunction "PWM1_35") (pintype "output"))
    )
    (net (code "112") (name "unconnected-(U2-PWM2-Pad36)") (class "Default")
      (node (ref "U2") (pin "36") (pinfunction "PWM2_36") (pintype "output"))
    )
    (net (code "113") (name "unconnected-(U2-PWRKEY_OUT-Pad2)") (class "Default")
      (node (ref "U2") (pin "2") (pinfunction "PWRKEY_OUT_2") (pintype "output"))
    )
    (net (code "114") (name "unconnected-(U2-RI-Pad4)") (class "Default")
      (node (ref "U2") (pin "4") (pinfunction "RI_4") (pintype "output"))
    )
    (net (code "115") (name "unconnected-(U2-RTS-Pad8)") (class "Default")
      (node (ref "U2") (pin "8") (pinfunction "RTS_8") (pintype "input"))
    )
    (net (code "116") (name "unconnected-(U2-SCL-Pad38)") (class "Default")
      (node (ref "U2") (pin "38") (pinfunction "SCL_38") (pintype "output"))
    )
    (net (code "117") (name "unconnected-(U2-SDA-Pad37)") (class "Default")
      (node (ref "U2") (pin "37") (pinfunction "SDA_37") (pintype "bidirectional"))
    )
    (net (code "118") (name "unconnected-(U2-SIM_PRESENCE-Pad34)") (class "Default")
      (node (ref "U2") (pin "34") (pinfunction "SIM_PRESENCE_34") (pintype "input"))
    )
    (net (code "119") (name "unconnected-(U2-SPK_N-Pad22)") (class "Default")
      (node (ref "U2") (pin "22") (pinfunction "SPK_N_22") (pintype "output"))
    )
    (net (code "120") (name "unconnected-(U2-SPK_P-Pad21)") (class "Default")
      (node (ref "U2") (pin "21") (pinfunction "SPK_P_21") (pintype "output"))
    )
    (net (code "121") (name "unconnected-(U2-STATUS-Pad66)") (class "Default")
      (node (ref "U2") (pin "66") (pinfunction "STATUS_66") (pintype "output"))
    )
    (net (code "122") (name "unconnected-(U2-VDD_EXT-Pad15)") (class "Default")
      (node (ref "U2") (pin "15") (pinfunction "VDD_EXT_15") (pintype "output"))
    )
    (net (code "123") (name "unconnected-(U2-VRTC-Pad26)") (class "Default")
      (node (ref "U2") (pin "26") (pinfunction "VRTC_26") (pintype "bidirectional"))
    )
    (net (code "124") (name "unconnected-(U4-AUX_CL-Pad7)") (class "Default")
      (node (ref "U4") (pin "7") (pinfunction "AUX_CL_7") (pintype "bidirectional"))
    )
    (net (code "125") (name "unconnected-(U4-AUX_DA-Pad6)") (class "Default")
      (node (ref "U4") (pin "6") (pinfunction "AUX_DA_6") (pintype "bidirectional"))
    )
    (net (code "126") (name "unconnected-(U4-INT-Pad12)") (class "Default")
      (node (ref "U4") (pin "12") (pinfunction "INT_12") (pintype "bidirectional"))
    )
    (net (code "127") (name "unconnected-(X1-Pad2)") (class "Default")
      (node (ref "X1") (pin "2") (pinfunction "2_2") (pintype "passive"))
    )
    (net (code "128") (name "unconnected-(X1-Pad3)") (class "Default")
      (node (ref "X1") (pin "3") (pinfunction "3_3") (pintype "passive"))
    )
    (net (code "129") (name "unconnected-(X1-Pad4)") (class "Default")
      (node (ref "X1") (pin "4") (pinfunction "4_4") (pintype "passive"))
    )
  )
)
